# bilancia_smart.net
KiCad netlist of a schematic drawn in EAGLE
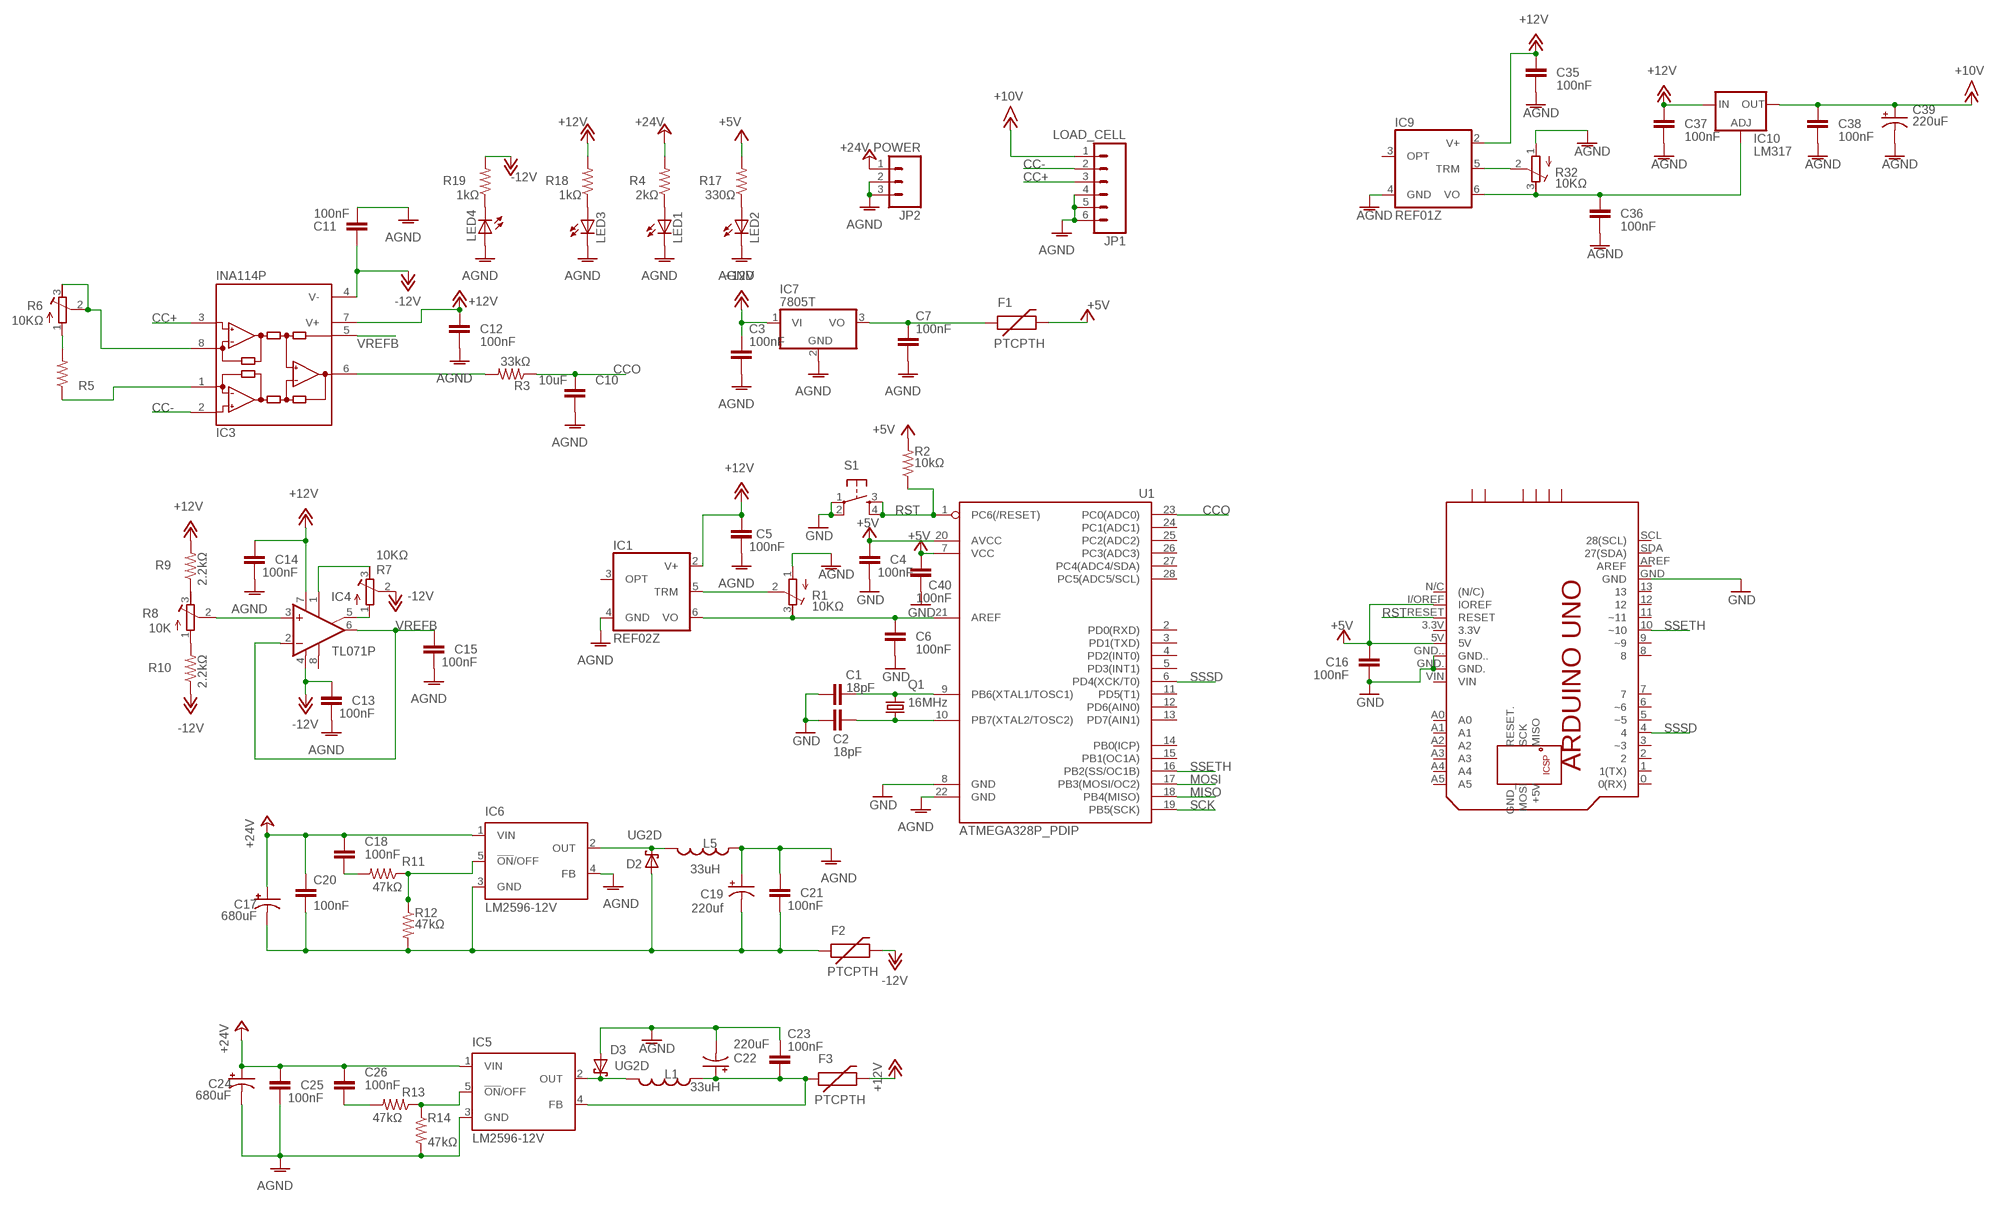
[diagram p0: schematic, sheet 1]

(export (version "E")
  (design (tool "Eeschema 10.0.6"))
  (components
    (comp (ref "C1")
      (value "18pF")
      (footprint "eagle-import:C2.5-2")
      (libsource (lib "eagle-import") (part "C2.5/2"))
    )
    (comp (ref "C2")
      (value "18pF")
      (footprint "eagle-import:C2.5-2")
      (libsource (lib "eagle-import") (part "C2.5/2"))
    )
    (comp (ref "C3")
      (value "100nF")
      (footprint "eagle-import:C2.5-2")
      (libsource (lib "eagle-import") (part "C2.5/2"))
    )
    (comp (ref "C4")
      (value "100nF")
      (footprint "eagle-import:C2.5-2")
      (libsource (lib "eagle-import") (part "C2.5/2"))
    )
    (comp (ref "C5")
      (value "100nF")
      (footprint "eagle-import:C2.5-2")
      (libsource (lib "eagle-import") (part "C2.5/2"))
    )
    (comp (ref "C6")
      (value "100nF")
      (footprint "eagle-import:C2.5-2")
      (libsource (lib "eagle-import") (part "C2.5/2"))
    )
    (comp (ref "C7")
      (value "100nF")
      (footprint "eagle-import:C2.5-2")
      (libsource (lib "eagle-import") (part "C2.5/2"))
    )
    (comp (ref "C10")
      (value "10uF")
      (footprint "eagle-import:C2.5-2")
      (libsource (lib "eagle-import") (part "C2.5/2"))
    )
    (comp (ref "C11")
      (value "100nF")
      (footprint "eagle-import:C2.5-2")
      (libsource (lib "eagle-import") (part "C2.5/2"))
    )
    (comp (ref "C12")
      (value "100nF")
      (footprint "eagle-import:C2.5-2")
      (libsource (lib "eagle-import") (part "C2.5/2"))
    )
    (comp (ref "C13")
      (value "100nF")
      (footprint "eagle-import:C2.5-2")
      (libsource (lib "eagle-import") (part "C2.5/2"))
    )
    (comp (ref "C14")
      (value "100nF")
      (footprint "eagle-import:C2.5-2")
      (libsource (lib "eagle-import") (part "C2.5/2"))
    )
    (comp (ref "C15")
      (value "100nF")
      (footprint "eagle-import:C2.5-2")
      (libsource (lib "eagle-import") (part "C2.5/2"))
    )
    (comp (ref "C16")
      (value "100nF")
      (footprint "eagle-import:C2.5-2")
      (libsource (lib "eagle-import") (part "C2.5/2"))
    )
    (comp (ref "C17")
      (value "680uF")
      (footprint "eagle-import:E5-8,5")
      (libsource (lib "eagle-import") (part "CPOL-USE5-8.5"))
    )
    (comp (ref "C18")
      (value "100nF")
      (footprint "eagle-import:C2.5-2")
      (libsource (lib "eagle-import") (part "C2.5/2"))
    )
    (comp (ref "C19")
      (value "220uf")
      (footprint "eagle-import:E5-8,5")
      (libsource (lib "eagle-import") (part "CPOL-USE5-8.5"))
    )
    (comp (ref "C20")
      (value "100nF")
      (footprint "eagle-import:C2.5-2")
      (libsource (lib "eagle-import") (part "C2.5/2"))
    )
    (comp (ref "C21")
      (value "100nF")
      (footprint "eagle-import:C2.5-2")
      (libsource (lib "eagle-import") (part "C2.5/2"))
    )
    (comp (ref "C22")
      (value "220uF")
      (footprint "eagle-import:E5-8,5")
      (libsource (lib "eagle-import") (part "CPOL-USE5-8.5"))
    )
    (comp (ref "C23")
      (value "100nF")
      (footprint "eagle-import:C2.5-2")
      (libsource (lib "eagle-import") (part "C2.5/2"))
    )
    (comp (ref "C24")
      (value "680uF")
      (footprint "eagle-import:E5-8,5")
      (libsource (lib "eagle-import") (part "CPOL-USE5-8.5"))
    )
    (comp (ref "C25")
      (value "100nF")
      (footprint "eagle-import:C2.5-2")
      (libsource (lib "eagle-import") (part "C2.5/2"))
    )
    (comp (ref "C26")
      (value "100nF")
      (footprint "eagle-import:C2.5-2")
      (libsource (lib "eagle-import") (part "C2.5/2"))
    )
    (comp (ref "C35")
      (value "100nF")
      (footprint "eagle-import:C2.5-2")
      (libsource (lib "eagle-import") (part "C2.5/2"))
    )
    (comp (ref "C36")
      (value "100nF")
      (footprint "eagle-import:C2.5-2")
      (libsource (lib "eagle-import") (part "C2.5/2"))
    )
    (comp (ref "C37")
      (value "100nF")
      (footprint "eagle-import:C2.5-2")
      (libsource (lib "eagle-import") (part "C2.5/2"))
    )
    (comp (ref "C38")
      (value "100nF")
      (footprint "eagle-import:C2.5-2")
      (libsource (lib "eagle-import") (part "C2.5/2"))
    )
    (comp (ref "C39")
      (value "220uF")
      (footprint "eagle-import:CPOL-RADIAL-100UF-25V")
      (libsource (lib "eagle-import") (part "CAP_POLPTH1"))
    )
    (comp (ref "C40")
      (value "100nF")
      (footprint "eagle-import:C2.5-2")
      (libsource (lib "eagle-import") (part "C2.5/2"))
    )
    (comp (ref "D2")
      (value "UG2D")
      (footprint "eagle-import:DO41-7")
      (libsource (lib "eagle-import") (part "SCHOTTKY-DIODEDO41-7"))
    )
    (comp (ref "D3")
      (value "UG2D")
      (footprint "eagle-import:DO41-7")
      (libsource (lib "eagle-import") (part "SCHOTTKY-DIODEDO41-7"))
    )
    (comp (ref "F1")
      (value "PTCPTH")
      (footprint "eagle-import:PTC")
      (libsource (lib "eagle-import") (part "PTCPTH"))
    )
    (comp (ref "F2")
      (value "PTCPTH")
      (footprint "eagle-import:PTC")
      (libsource (lib "eagle-import") (part "PTCPTH"))
    )
    (comp (ref "F3")
      (value "PTCPTH")
      (footprint "eagle-import:PTC")
      (libsource (lib "eagle-import") (part "PTCPTH"))
    )
    (comp (ref "IC1")
      (value "REF02Z")
      (footprint "eagle-import:DIL08")
      (libsource (lib "eagle-import") (part "REF02Z"))
    )
    (comp (ref "IC3")
      (value "INA114P")
      (footprint "eagle-import:DIL08")
      (fields (field (name "MF") "TEXAS INSTRUMENTS") (field (name "MPN") "INA114BP"))
      (libsource (lib "eagle-import") (part "INA114P"))
    )
    (comp (ref "IC4")
      (value "TL071P")
      (footprint "eagle-import:DIL08")
      (libsource (lib "eagle-import") (part "TL071P"))
    )
    (comp (ref "IC5")
      (value "LM2596-12V")
      (footprint "eagle-import:T05D")
      (fields (field (name "MPN") "LM2596T-ADJ/LF02"))
      (libsource (lib "eagle-import") (part "LM2596T"))
    )
    (comp (ref "IC6")
      (value "LM2596-12V")
      (footprint "eagle-import:T05D")
      (fields (field (name "MPN") "LM2596T-ADJ/LF02"))
      (libsource (lib "eagle-import") (part "LM2596T"))
    )
    (comp (ref "IC7")
      (value "7805T")
      (footprint "eagle-import:TO220H")
      (libsource (lib "eagle-import") (part "78T05"))
    )
    (comp (ref "IC9")
      (value "REF01Z")
      (footprint "eagle-import:DIL08")
      (libsource (lib "eagle-import") (part "REF01Z"))
    )
    (comp (ref "IC10")
      (value "LM317")
      (footprint "eagle-import:317TS")
      (libsource (lib "eagle-import") (part "LM317TS"))
    )
    (comp (ref "JP1")
      (value "LOAD_CELL")
      (footprint "eagle-import:1X06")
      (libsource (lib "eagle-import") (part "M06SIP"))
    )
    (comp (ref "JP2")
      (value "POWER")
      (footprint "eagle-import:1X03")
      (libsource (lib "eagle-import") (part "M03PTH"))
    )
    (comp (ref "L1")
      (value "33uH")
      (footprint "eagle-import:RLB0912")
      (libsource (lib "eagle-import") (part "INDUCTORRLB0912"))
    )
    (comp (ref "L5")
      (value "33uH")
      (footprint "eagle-import:RLB0912")
      (libsource (lib "eagle-import") (part "INDUCTORRLB0912"))
    )
    (comp (ref "LED1")
      (value "MINIMIDI_LED5MM")
      (footprint "eagle-import:MINIMIDI_LED5MM")
      (libsource (lib "eagle-import") (part "MINIMIDI_LED5MM"))
    )
    (comp (ref "LED2")
      (value "MINIMIDI_LED5MM")
      (footprint "eagle-import:MINIMIDI_LED5MM")
      (libsource (lib "eagle-import") (part "MINIMIDI_LED5MM"))
    )
    (comp (ref "LED3")
      (value "MINIMIDI_LED5MM")
      (footprint "eagle-import:MINIMIDI_LED5MM")
      (libsource (lib "eagle-import") (part "MINIMIDI_LED5MM"))
    )
    (comp (ref "LED4")
      (value "MINIMIDI_LED5MM")
      (footprint "eagle-import:MINIMIDI_LED5MM")
      (libsource (lib "eagle-import") (part "MINIMIDI_LED5MM"))
    )
    (comp (ref "PCB1")
      (value "ARDUINO_UNO")
      (footprint "eagle-import:ARDUINO_UNO")
      (libsource (lib "eagle-import") (part "ARDUINO_UNO"))
    )
    (comp (ref "Q1")
      (value "16MHz")
      (footprint "eagle-import:HC49_S")
      (libsource (lib "eagle-import") (part "CRYSTALHC49S"))
    )
    (comp (ref "R1")
      (value "10KΩ")
      (footprint "eagle-import:RTRIM64W")
      (libsource (lib "eagle-import") (part "R-TRIMM64W"))
    )
    (comp (ref "R2")
      (value "10kΩ")
      (footprint "eagle-import:0207_10")
      (libsource (lib "eagle-import") (part "R-US_0207/10"))
    )
    (comp (ref "R3")
      (value "33kΩ")
      (footprint "eagle-import:0207_10")
      (libsource (lib "eagle-import") (part "R-US_0207/10"))
    )
    (comp (ref "R4")
      (value "2kΩ")
      (footprint "eagle-import:0207_10")
      (libsource (lib "eagle-import") (part "R-US_0207/10"))
    )
    (comp (ref "R5")
      (value "R-US_0207/10")
      (footprint "eagle-import:0207_10")
      (libsource (lib "eagle-import") (part "R-US_0207/10"))
    )
    (comp (ref "R6")
      (value "10KΩ")
      (footprint "eagle-import:RTRIM64W")
      (libsource (lib "eagle-import") (part "R-TRIMM64W"))
    )
    (comp (ref "R7")
      (value "10KΩ")
      (footprint "eagle-import:RTRIM64W")
      (libsource (lib "eagle-import") (part "R-TRIMM64W"))
    )
    (comp (ref "R8")
      (value "10K")
      (footprint "eagle-import:RTRIM64W")
      (libsource (lib "eagle-import") (part "R-TRIMM64W"))
    )
    (comp (ref "R9")
      (value "2.2kΩ")
      (footprint "eagle-import:0207_10")
      (libsource (lib "eagle-import") (part "R-US_0207/10"))
    )
    (comp (ref "R10")
      (value "2.2kΩ")
      (footprint "eagle-import:0207_10")
      (libsource (lib "eagle-import") (part "R-US_0207/10"))
    )
    (comp (ref "R11")
      (value "47kΩ")
      (footprint "eagle-import:0207_2V")
      (libsource (lib "eagle-import") (part "R-US_0207/2V"))
    )
    (comp (ref "R12")
      (value "47kΩ")
      (footprint "eagle-import:0207_2V")
      (libsource (lib "eagle-import") (part "R-US_0207/2V"))
    )
    (comp (ref "R13")
      (value "47kΩ")
      (footprint "eagle-import:0207_2V")
      (libsource (lib "eagle-import") (part "R-US_0207/2V"))
    )
    (comp (ref "R14")
      (value "47kΩ")
      (footprint "eagle-import:0207_2V")
      (libsource (lib "eagle-import") (part "R-US_0207/2V"))
    )
    (comp (ref "R17")
      (value "330Ω")
      (footprint "eagle-import:0207_10")
      (libsource (lib "eagle-import") (part "R-US_0207/10"))
    )
    (comp (ref "R18")
      (value "1kΩ")
      (footprint "eagle-import:0207_10")
      (libsource (lib "eagle-import") (part "R-US_0207/10"))
    )
    (comp (ref "R19")
      (value "1kΩ")
      (footprint "eagle-import:0207_10")
      (libsource (lib "eagle-import") (part "R-US_0207/10"))
    )
    (comp (ref "R32")
      (value "10KΩ")
      (footprint "eagle-import:RTRIM64W")
      (libsource (lib "eagle-import") (part "R-TRIMM64W"))
    )
    (comp (ref "S1")
      (value "TAC_SWITCHPTH")
      (footprint "eagle-import:TACTILE-PTH")
      (libsource (lib "eagle-import") (part "TAC_SWITCHPTH"))
    )
    (comp (ref "U1")
      (value "ATMEGA328P_PDIP")
      (footprint "eagle-import:DIL28-3")
      (libsource (lib "eagle-import") (part "ATMEGA328P_PDIP"))
    )
  )
  (nets
    (net (code "1") (name "+5V") (class "Default")
      (node (ref "C16") (pin "2") (pinfunction "2_2") (pintype "passive"))
      (node (ref "C4") (pin "2") (pinfunction "2_2") (pintype "passive"))
      (node (ref "C40") (pin "2") (pinfunction "2_2") (pintype "passive"))
      (node (ref "F1") (pin "P$2") (pinfunction "2_P$2") (pintype "bidirectional"))
      (node (ref "PCB1") (pin "5V") (pinfunction "5V_5V") (pintype "bidirectional"))
      (node (ref "PCB1") (pin "I/OREF") (pinfunction "IOREF_I/OREF") (pintype "bidirectional"))
      (node (ref "R17") (pin "2") (pinfunction "2_2") (pintype "passive"))
      (node (ref "R2") (pin "2") (pinfunction "2_2") (pintype "passive"))
      (node (ref "U1") (pin "20") (pinfunction "AVCC_20") (pintype "bidirectional"))
      (node (ref "U1") (pin "7") (pinfunction "VCC_7") (pintype "bidirectional"))
    )
    (net (code "2") (name "+10V") (class "Default")
      (node (ref "C38") (pin "2") (pinfunction "2_2") (pintype "passive"))
      (node (ref "C39") (pin "1") (pinfunction "+_1") (pintype "passive"))
      (node (ref "IC10") (pin "2") (pinfunction "OUT_2") (pintype "passive"))
      (node (ref "JP1") (pin "1") (pinfunction "1_1") (pintype "passive"))
    )
    (net (code "3") (name "+12V") (class "Default")
      (node (ref "C12") (pin "2") (pinfunction "2_2") (pintype "passive"))
      (node (ref "C14") (pin "2") (pinfunction "2_2") (pintype "passive"))
      (node (ref "C3") (pin "2") (pinfunction "2_2") (pintype "passive"))
      (node (ref "C35") (pin "2") (pinfunction "2_2") (pintype "passive"))
      (node (ref "C37") (pin "2") (pinfunction "2_2") (pintype "passive"))
      (node (ref "C5") (pin "1") (pinfunction "1_1") (pintype "passive"))
      (node (ref "F3") (pin "P$2") (pinfunction "2_P$2") (pintype "bidirectional"))
      (node (ref "IC1") (pin "2") (pinfunction "V+_2") (pintype "power_in"))
      (node (ref "IC10") (pin "3") (pinfunction "IN_3") (pintype "input"))
      (node (ref "IC3") (pin "7") (pinfunction "V+_7") (pintype "power_in"))
      (node (ref "IC4") (pin "7") (pinfunction "V+_7") (pintype "power_in"))
      (node (ref "IC7") (pin "1") (pinfunction "VI_1") (pintype "input"))
      (node (ref "IC9") (pin "2") (pinfunction "V+_2") (pintype "power_in"))
      (node (ref "R18") (pin "2") (pinfunction "2_2") (pintype "passive"))
      (node (ref "R9") (pin "2") (pinfunction "2_2") (pintype "passive"))
    )
    (net (code "4") (name "+24V") (class "Default")
      (node (ref "C17") (pin "+") (pinfunction "+_+") (pintype "passive"))
      (node (ref "C18") (pin "1") (pinfunction "1_1") (pintype "passive"))
      (node (ref "C20") (pin "1") (pinfunction "1_1") (pintype "passive"))
      (node (ref "C24") (pin "+") (pinfunction "+_+") (pintype "passive"))
      (node (ref "C25") (pin "1") (pinfunction "1_1") (pintype "passive"))
      (node (ref "C26") (pin "1") (pinfunction "1_1") (pintype "passive"))
      (node (ref "IC5") (pin "1") (pinfunction "VIN_1") (pintype "input"))
      (node (ref "IC6") (pin "1") (pinfunction "VIN_1") (pintype "input"))
      (node (ref "JP2") (pin "1") (pinfunction "1_1") (pintype "passive"))
      (node (ref "R4") (pin "2") (pinfunction "2_2") (pintype "passive"))
    )
    (net (code "5") (name "-12V") (class "Default")
      (node (ref "C11") (pin "2") (pinfunction "2_2") (pintype "passive"))
      (node (ref "C13") (pin "2") (pinfunction "2_2") (pintype "passive"))
      (node (ref "F2") (pin "P$2") (pinfunction "2_P$2") (pintype "bidirectional"))
      (node (ref "IC3") (pin "4") (pinfunction "V-_4") (pintype "power_in"))
      (node (ref "IC4") (pin "4") (pinfunction "V-_4") (pintype "power_in"))
      (node (ref "R10") (pin "1") (pinfunction "1_1") (pintype "passive"))
      (node (ref "R19") (pin "2") (pinfunction "2_2") (pintype "passive"))
      (node (ref "R7") (pin "2") (pinfunction "S_2") (pintype "passive"))
    )
    (net (code "6") (name "/CC+") (class "Default")
      (node (ref "IC3") (pin "3") (pinfunction "+IN_3") (pintype "input"))
      (node (ref "JP1") (pin "3") (pinfunction "3_3") (pintype "passive"))
    )
    (net (code "7") (name "/CC-") (class "Default")
      (node (ref "IC3") (pin "2") (pinfunction "-IN_2") (pintype "input"))
      (node (ref "JP1") (pin "2") (pinfunction "2_2") (pintype "passive"))
    )
    (net (code "8") (name "/CCO") (class "Default")
      (node (ref "C10") (pin "2") (pinfunction "2_2") (pintype "passive"))
      (node (ref "R3") (pin "1") (pinfunction "1_1") (pintype "passive"))
      (node (ref "U1") (pin "23") (pinfunction "PC0(ADC0)_23") (pintype "bidirectional"))
    )
    (net (code "9") (name "/MISO") (class "Default")
      (node (ref "U1") (pin "18") (pinfunction "PB4(MISO)_18") (pintype "bidirectional"))
    )
    (net (code "10") (name "/MOSI") (class "Default")
      (node (ref "U1") (pin "17") (pinfunction "PB3(MOSI/OC2)_17") (pintype "bidirectional"))
    )
    (net (code "11") (name "/RST") (class "Default")
      (node (ref "PCB1") (pin "RESET") (pinfunction "RESET_RESET") (pintype "bidirectional"))
      (node (ref "R2") (pin "1") (pinfunction "1_1") (pintype "passive"))
      (node (ref "S1") (pin "3") (pinfunction "3_3") (pintype "passive"))
      (node (ref "S1") (pin "4") (pinfunction "4_4") (pintype "passive"))
      (node (ref "U1") (pin "1") (pinfunction "PC6(/RESET)_1") (pintype "bidirectional"))
    )
    (net (code "12") (name "/SCK") (class "Default")
      (node (ref "U1") (pin "19") (pinfunction "PB5(SCK)_19") (pintype "bidirectional"))
    )
    (net (code "13") (name "/SSETH") (class "Default")
      (node (ref "PCB1") (pin "10") (pinfunction "~{10}_10") (pintype "bidirectional"))
      (node (ref "U1") (pin "16") (pinfunction "PB2(SS/OC1B)_16") (pintype "bidirectional"))
    )
    (net (code "14") (name "/SSSD") (class "Default")
      (node (ref "PCB1") (pin "4") (pinfunction "4_4") (pintype "bidirectional"))
      (node (ref "U1") (pin "6") (pinfunction "PD4(XCK/T0)_6") (pintype "bidirectional"))
    )
    (net (code "15") (name "/VREFB") (class "Default")
      (node (ref "C15") (pin "2") (pinfunction "2_2") (pintype "passive"))
      (node (ref "IC3") (pin "5") (pinfunction "REF_5") (pintype "passive"))
      (node (ref "IC4") (pin "2") (pinfunction "-IN_2") (pintype "input"))
      (node (ref "IC4") (pin "6") (pinfunction "OUT_6") (pintype "output"))
    )
    (net (code "16") (name "AGND") (class "Default")
      (node (ref "C10") (pin "1") (pinfunction "1_1") (pintype "passive"))
      (node (ref "C11") (pin "1") (pinfunction "1_1") (pintype "passive"))
      (node (ref "C12") (pin "1") (pinfunction "1_1") (pintype "passive"))
      (node (ref "C13") (pin "1") (pinfunction "1_1") (pintype "passive"))
      (node (ref "C14") (pin "1") (pinfunction "1_1") (pintype "passive"))
      (node (ref "C15") (pin "1") (pinfunction "1_1") (pintype "passive"))
      (node (ref "C19") (pin "+") (pinfunction "+_+") (pintype "passive"))
      (node (ref "C21") (pin "1") (pinfunction "1_1") (pintype "passive"))
      (node (ref "C22") (pin "-") (pinfunction "-_-") (pintype "passive"))
      (node (ref "C23") (pin "2") (pinfunction "2_2") (pintype "passive"))
      (node (ref "C24") (pin "-") (pinfunction "-_-") (pintype "passive"))
      (node (ref "C25") (pin "2") (pinfunction "2_2") (pintype "passive"))
      (node (ref "C3") (pin "1") (pinfunction "1_1") (pintype "passive"))
      (node (ref "C35") (pin "1") (pinfunction "1_1") (pintype "passive"))
      (node (ref "C36") (pin "1") (pinfunction "1_1") (pintype "passive"))
      (node (ref "C37") (pin "1") (pinfunction "1_1") (pintype "passive"))
      (node (ref "C38") (pin "1") (pinfunction "1_1") (pintype "passive"))
      (node (ref "C39") (pin "2") (pinfunction "-_2") (pintype "passive"))
      (node (ref "C5") (pin "2") (pinfunction "2_2") (pintype "passive"))
      (node (ref "C7") (pin "1") (pinfunction "1_1") (pintype "passive"))
      (node (ref "D3") (pin "A") (pinfunction "A_A") (pintype "passive"))
      (node (ref "IC1") (pin "4") (pinfunction "GND_4") (pintype "power_in"))
      (node (ref "IC5") (pin "3") (pinfunction "GND_3") (pintype "power_in"))
      (node (ref "IC6") (pin "4") (pinfunction "FB_4") (pintype "input"))
      (node (ref "IC7") (pin "2") (pinfunction "GND_2") (pintype "passive"))
      (node (ref "IC9") (pin "4") (pinfunction "GND_4") (pintype "power_in"))
      (node (ref "JP1") (pin "4") (pinfunction "4_4") (pintype "passive"))
      (node (ref "JP1") (pin "5") (pinfunction "5_5") (pintype "passive"))
      (node (ref "JP1") (pin "6") (pinfunction "6_6") (pintype "passive"))
      (node (ref "JP2") (pin "2") (pinfunction "2_2") (pintype "passive"))
      (node (ref "JP2") (pin "3") (pinfunction "3_3") (pintype "passive"))
      (node (ref "L5") (pin "1") (pinfunction "1_1") (pintype "passive"))
      (node (ref "LED1") (pin "K") (pinfunction "C_K") (pintype "passive"))
      (node (ref "LED2") (pin "K") (pinfunction "C_K") (pintype "passive"))
      (node (ref "LED3") (pin "K") (pinfunction "C_K") (pintype "passive"))
      (node (ref "LED4") (pin "A") (pinfunction "A_A") (pintype "passive"))
      (node (ref "R1") (pin "1") (pinfunction "E_1") (pintype "passive"))
      (node (ref "R14") (pin "2") (pinfunction "2_2") (pintype "passive"))
      (node (ref "R32") (pin "1") (pinfunction "E_1") (pintype "passive"))
      (node (ref "U1") (pin "22") (pinfunction "GND_22") (pintype "bidirectional"))
    )
    (net (code "17") (name "GND") (class "Default")
      (node (ref "C1") (pin "1") (pinfunction "1_1") (pintype "passive"))
      (node (ref "C16") (pin "1") (pinfunction "1_1") (pintype "passive"))
      (node (ref "C2") (pin "1") (pinfunction "1_1") (pintype "passive"))
      (node (ref "C4") (pin "1") (pinfunction "1_1") (pintype "passive"))
      (node (ref "C40") (pin "1") (pinfunction "1_1") (pintype "passive"))
      (node (ref "C6") (pin "1") (pinfunction "1_1") (pintype "passive"))
      (node (ref "PCB1") (pin "GND") (pinfunction "GND_GND") (pintype "bidirectional"))
      (node (ref "PCB1") (pin "GND.") (pinfunction "GND._GND.") (pintype "bidirectional"))
      (node (ref "PCB1") (pin "GND..") (pinfunction "GND.._GND..") (pintype "bidirectional"))
      (node (ref "S1") (pin "1") (pinfunction "1_1") (pintype "passive"))
      (node (ref "S1") (pin "2") (pinfunction "2_2") (pintype "passive"))
      (node (ref "U1") (pin "8") (pinfunction "GND_8") (pintype "bidirectional"))
    )
    (net (code "18") (name "Net-(C18-Pad2)") (class "Default")
      (node (ref "C18") (pin "2") (pinfunction "2_2") (pintype "passive"))
      (node (ref "R11") (pin "2") (pinfunction "2_2") (pintype "passive"))
    )
    (net (code "19") (name "Net-(C26-Pad2)") (class "Default")
      (node (ref "C26") (pin "2") (pinfunction "2_2") (pintype "passive"))
      (node (ref "R13") (pin "2") (pinfunction "2_2") (pintype "passive"))
    )
    (net (code "20") (name "Net-(F1-1)") (class "Default")
      (node (ref "C7") (pin "2") (pinfunction "2_2") (pintype "passive"))
      (node (ref "F1") (pin "P$1") (pinfunction "1_P$1") (pintype "bidirectional"))
      (node (ref "IC7") (pin "3") (pinfunction "VO_3") (pintype "passive"))
    )
    (net (code "21") (name "Net-(F2-1)") (class "Default")
      (node (ref "C17") (pin "-") (pinfunction "-_-") (pintype "passive"))
      (node (ref "C19") (pin "-") (pinfunction "-_-") (pintype "passive"))
      (node (ref "C20") (pin "2") (pinfunction "2_2") (pintype "passive"))
      (node (ref "C21") (pin "2") (pinfunction "2_2") (pintype "passive"))
      (node (ref "D2") (pin "A") (pinfunction "A_A") (pintype "passive"))
      (node (ref "F2") (pin "P$1") (pinfunction "1_P$1") (pintype "bidirectional"))
      (node (ref "IC6") (pin "3") (pinfunction "GND_3") (pintype "power_in"))
      (node (ref "R12") (pin "2") (pinfunction "2_2") (pintype "passive"))
    )
    (net (code "22") (name "Net-(F3-1)") (class "Default")
      (node (ref "C22") (pin "+") (pinfunction "+_+") (pintype "passive"))
      (node (ref "C23") (pin "1") (pinfunction "1_1") (pintype "passive"))
      (node (ref "F3") (pin "P$1") (pinfunction "1_P$1") (pintype "bidirectional"))
      (node (ref "IC5") (pin "4") (pinfunction "FB_4") (pintype "input"))
      (node (ref "L1") (pin "1") (pinfunction "1_1") (pintype "passive"))
    )
    (net (code "23") (name "Net-(IC1-TRM)") (class "Default")
      (node (ref "IC1") (pin "5") (pinfunction "TRM_5") (pintype "input"))
      (node (ref "R1") (pin "2") (pinfunction "S_2") (pintype "passive"))
    )
    (net (code "24") (name "Net-(IC1-VO)") (class "Default")
      (node (ref "C6") (pin "2") (pinfunction "2_2") (pintype "passive"))
      (node (ref "IC1") (pin "6") (pinfunction "VO_6") (pintype "output"))
      (node (ref "R1") (pin "3") (pinfunction "A_3") (pintype "passive"))
      (node (ref "U1") (pin "21") (pinfunction "AREF_21") (pintype "bidirectional"))
    )
    (net (code "25") (name "Net-(IC3-OUT)") (class "Default")
      (node (ref "IC3") (pin "6") (pinfunction "OUT_6") (pintype "output"))
      (node (ref "R3") (pin "2") (pinfunction "2_2") (pintype "passive"))
    )
    (net (code "26") (name "Net-(IC3-RG-Pad1)") (class "Default")
      (node (ref "IC3") (pin "1") (pinfunction "RG_1") (pintype "passive"))
      (node (ref "R5") (pin "1") (pinfunction "1_1") (pintype "passive"))
    )
    (net (code "27") (name "Net-(IC4-+IN)") (class "Default")
      (node (ref "IC4") (pin "3") (pinfunction "+IN_3") (pintype "input"))
      (node (ref "R8") (pin "2") (pinfunction "S_2") (pintype "passive"))
    )
    (net (code "28") (name "Net-(IC4-ON1)") (class "Default")
      (node (ref "IC4") (pin "1") (pinfunction "ON1_1") (pintype "passive"))
      (node (ref "R7") (pin "3") (pinfunction "A_3") (pintype "passive"))
    )
    (net (code "29") (name "Net-(IC4-ON2)") (class "Default")
      (node (ref "IC4") (pin "5") (pinfunction "ON2_5") (pintype "passive"))
      (node (ref "R7") (pin "1") (pinfunction "E_1") (pintype "passive"))
    )
    (net (code "30") (name "Net-(IC5-OUT)") (class "Default")
      (node (ref "D3") (pin "C") (pinfunction "C_C") (pintype "passive"))
      (node (ref "IC5") (pin "2") (pinfunction "OUT_2") (pintype "output"))
      (node (ref "L1") (pin "2") (pinfunction "2_2") (pintype "passive"))
    )
    (net (code "31") (name "Net-(IC5-~{ON}{slash}OFF)") (class "Default")
      (node (ref "IC5") (pin "5") (pinfunction "~{ON}/OFF_5") (pintype "input"))
      (node (ref "R13") (pin "1") (pinfunction "1_1") (pintype "passive"))
      (node (ref "R14") (pin "1") (pinfunction "1_1") (pintype "passive"))
    )
    (net (code "32") (name "Net-(IC6-OUT)") (class "Default")
      (node (ref "D2") (pin "C") (pinfunction "C_C") (pintype "passive"))
      (node (ref "IC6") (pin "2") (pinfunction "OUT_2") (pintype "output"))
      (node (ref "L5") (pin "2") (pinfunction "2_2") (pintype "passive"))
    )
    (net (code "33") (name "Net-(IC6-~{ON}{slash}OFF)") (class "Default")
      (node (ref "IC6") (pin "5") (pinfunction "~{ON}/OFF_5") (pintype "input"))
      (node (ref "R11") (pin "1") (pinfunction "1_1") (pintype "passive"))
      (node (ref "R12") (pin "1") (pinfunction "1_1") (pintype "passive"))
    )
    (net (code "34") (name "Net-(IC9-TRM)") (class "Default")
      (node (ref "IC9") (pin "5") (pinfunction "TRM_5") (pintype "input"))
      (node (ref "R32") (pin "2") (pinfunction "S_2") (pintype "passive"))
    )
    (net (code "35") (name "Net-(IC10-ADJ)") (class "Default")
      (node (ref "C36") (pin "2") (pinfunction "2_2") (pintype "passive"))
      (node (ref "IC10") (pin "1") (pinfunction "ADJ_1") (pintype "input"))
      (node (ref "IC9") (pin "6") (pinfunction "VO_6") (pintype "output"))
      (node (ref "R32") (pin "3") (pinfunction "A_3") (pintype "passive"))
    )
    (net (code "36") (name "Net-(LED1-PadA)") (class "Default")
      (node (ref "LED1") (pin "A") (pinfunction "A_A") (pintype "passive"))
      (node (ref "R4") (pin "1") (pinfunction "1_1") (pintype "passive"))
    )
    (net (code "37") (name "Net-(LED2-PadA)") (class "Default")
      (node (ref "LED2") (pin "A") (pinfunction "A_A") (pintype "passive"))
      (node (ref "R17") (pin "1") (pinfunction "1_1") (pintype "passive"))
    )
    (net (code "38") (name "Net-(LED3-PadA)") (class "Default")
      (node (ref "LED3") (pin "A") (pinfunction "A_A") (pintype "passive"))
      (node (ref "R18") (pin "1") (pinfunction "1_1") (pintype "passive"))
    )
    (net (code "39") (name "Net-(LED4-C)") (class "Default")
      (node (ref "LED4") (pin "K") (pinfunction "C_K") (pintype "passive"))
      (node (ref "R19") (pin "1") (pinfunction "1_1") (pintype "passive"))
    )
    (net (code "40") (name "Net-(R6-A)") (class "Default")
      (node (ref "IC3") (pin "8") (pinfunction "RG_8") (pintype "passive"))
      (node (ref "R6") (pin "2") (pinfunction "S_2") (pintype "passive"))
      (node (ref "R6") (pin "3") (pinfunction "A_3") (pintype "passive"))
    )
    (net (code "41") (name "Net-(R6-E)") (class "Default")
      (node (ref "R5") (pin "2") (pinfunction "2_2") (pintype "passive"))
      (node (ref "R6") (pin "1") (pinfunction "E_1") (pintype "passive"))
    )
    (net (code "42") (name "Net-(R8-A)") (class "Default")
      (node (ref "R8") (pin "3") (pinfunction "A_3") (pintype "passive"))
      (node (ref "R9") (pin "1") (pinfunction "1_1") (pintype "passive"))
    )
    (net (code "43") (name "Net-(R8-E)") (class "Default")
      (node (ref "R10") (pin "2") (pinfunction "2_2") (pintype "passive"))
      (node (ref "R8") (pin "1") (pinfunction "E_1") (pintype "passive"))
    )
    (net (code "44") (name "Net-(U1-PB6(XTAL1{slash}TOSC1))") (class "Default")
      (node (ref "C1") (pin "2") (pinfunction "2_2") (pintype "passive"))
      (node (ref "Q1") (pin "1") (pinfunction "1_1") (pintype "passive"))
      (node (ref "U1") (pin "9") (pinfunction "PB6(XTAL1/TOSC1)_9") (pintype "bidirectional"))
    )
    (net (code "45") (name "Net-(U1-PB7(XTAL2{slash}TOSC2))") (class "Default")
      (node (ref "C2") (pin "2") (pinfunction "2_2") (pintype "passive"))
      (node (ref "Q1") (pin "2") (pinfunction "2_2") (pintype "passive"))
      (node (ref "U1") (pin "10") (pinfunction "PB7(XTAL2/TOSC2)_10") (pintype "bidirectional"))
    )
    (net (code "46") (name "unconnected-(IC1-OPT-Pad3)") (class "Default")
      (node (ref "IC1") (pin "3") (pinfunction "OPT_3") (pintype "output"))
    )
    (net (code "47") (name "unconnected-(IC4-OPT-Pad8)") (class "Default")
      (node (ref "IC4") (pin "8") (pinfunction "OPT_8") (pintype "passive"))
    )
    (net (code "48") (name "unconnected-(IC9-OPT-Pad3)") (class "Default")
      (node (ref "IC9") (pin "3") (pinfunction "OPT_3") (pintype "output"))
    )
    (net (code "49") (name "unconnected-(PCB1-(N{slash}C)-PadN{slash}C)") (class "Default")
      (node (ref "PCB1") (pin "N/C") (pinfunction "(N/C)_N/C") (pintype "bidirectional"))
    )
    (net (code "50") (name "unconnected-(PCB1-0(RX)-Pad0)") (class "Default")
      (node (ref "PCB1") (pin "0") (pinfunction "0(RX)_0") (pintype "bidirectional"))
    )
    (net (code "51") (name "unconnected-(PCB1-1(TX)-Pad1)") (class "Default")
      (node (ref "PCB1") (pin "1") (pinfunction "1(TX)_1") (pintype "bidirectional"))
    )
    (net (code "52") (name "unconnected-(PCB1-27(SDA)-PadSDA)") (class "Default")
      (node (ref "PCB1") (pin "SDA") (pinfunction "27(SDA)_SDA") (pintype "bidirectional"))
    )
    (net (code "53") (name "unconnected-(PCB1-28(SCL)-PadSCL)") (class "Default")
      (node (ref "PCB1") (pin "SCL") (pinfunction "28(SCL)_SCL") (pintype "bidirectional"))
    )
    (net (code "54") (name "unconnected-(PCB1-Pad+5V)") (class "Default")
      (node (ref "PCB1") (pin "+5V") (pinfunction "+5V_+5V") (pintype "bidirectional"))
    )
    (net (code "55") (name "unconnected-(PCB1-Pad2)") (class "Default")
      (node (ref "PCB1") (pin "2") (pinfunction "2_2") (pintype "bidirectional"))
    )
    (net (code "56") (name "unconnected-(PCB1-Pad3.3V)") (class "Default")
      (node (ref "PCB1") (pin "3.3V") (pinfunction "3.3V_3.3V") (pintype "bidirectional"))
    )
    (net (code "57") (name "unconnected-(PCB1-Pad7)") (class "Default")
      (node (ref "PCB1") (pin "7") (pinfunction "7_7") (pintype "bidirectional"))
    )
    (net (code "58") (name "unconnected-(PCB1-Pad8)") (class "Default")
      (node (ref "PCB1") (pin "8") (pinfunction "8_8") (pintype "bidirectional"))
    )
    (net (code "59") (name "unconnected-(PCB1-Pad12)") (class "Default")
      (node (ref "PCB1") (pin "12") (pinfunction "12_12") (pintype "bidirectional"))
    )
    (net (code "60") (name "unconnected-(PCB1-Pad13)") (class "Default")
      (node (ref "PCB1") (pin "13") (pinfunction "13_13") (pintype "bidirectional"))
    )
    (net (code "61") (name "unconnected-(PCB1-Pad<PWR>+V)") (class "Default")
      (node (ref "PCB1") (pin "<PWR>+V") (pinfunction "<PWR>+V_<PWR>+V") (pintype "bidirectional"))
    )
    (net (code "62") (name "unconnected-(PCB1-Pad<PWR>-V)") (class "Default")
      (node (ref "PCB1") (pin "<PWR>-V") (pinfunction "<PWR>-V_<PWR>-V") (pintype "bidirectional"))
    )
    (net (code "63") (name "unconnected-(PCB1-Pad<USB>+V)") (class "Default")
      (node (ref "PCB1") (pin "<USB>+V") (pinfunction "<USB>+V_<USB>+V") (pintype "bidirectional"))
    )
    (net (code "64") (name "unconnected-(PCB1-Pad<USB>D+)") (class "Default")
      (node (ref "PCB1") (pin "<USB>D+") (pinfunction "<USB>D+_<USB>D+") (pintype "bidirectional"))
    )
    (net (code "65") (name "unconnected-(PCB1-Pad<USB>D-)") (class "Default")
      (node (ref "PCB1") (pin "<USB>D-") (pinfunction "<USB>D-_<USB>D-") (pintype "bidirectional"))
    )
    (net (code "66") (name "unconnected-(PCB1-Pad<USB>GND)") (class "Default")
      (node (ref "PCB1") (pin "<USB>GND") (pinfunction "<USB>GND_<USB>GND") (pintype "bidirectional"))
    )
    (net (code "67") (name "unconnected-(PCB1-PadA0)") (class "Default")
      (node (ref "PCB1") (pin "A0") (pinfunction "A0_A0") (pintype "bidirectional"))
    )
    (net (code "68") (name "unconnected-(PCB1-PadA1)") (class "Default")
      (node (ref "PCB1") (pin "A1") (pinfunction "A1_A1") (pintype "bidirectional"))
    )
    (net (code "69") (name "unconnected-(PCB1-PadA2)") (class "Default")
      (node (ref "PCB1") (pin "A2") (pinfunction "A2_A2") (pintype "bidirectional"))
    )
    (net (code "70") (name "unconnected-(PCB1-PadA3)") (class "Default")
      (node (ref "PCB1") (pin "A3") (pinfunction "A3_A3") (pintype "bidirectional"))
    )
    (net (code "71") (name "unconnected-(PCB1-PadA4)") (class "Default")
      (node (ref "PCB1") (pin "A4") (pinfunction "A4_A4") (pintype "bidirectional"))
    )
    (net (code "72") (name "unconnected-(PCB1-PadA5)") (class "Default")
      (node (ref "PCB1") (pin "A5") (pinfunction "A5_A5") (pintype "bidirectional"))
    )
    (net (code "73") (name "unconnected-(PCB1-PadAREF)") (class "Default")
      (node (ref "PCB1") (pin "AREF") (pinfunction "AREF_AREF") (pintype "bidirectional"))
    )
    (net (code "74") (name "unconnected-(PCB1-PadGND_)") (class "Default")
      (node (ref "PCB1") (pin "GND_") (pinfunction "GND__GND_") (pintype "bidirectional"))
    )
    (net (code "75") (name "unconnected-(PCB1-PadMISO)") (class "Default")
      (node (ref "PCB1") (pin "MISO") (pinfunction "MISO_MISO") (pintype "bidirectional"))
    )
    (net (code "76") (name "unconnected-(PCB1-PadMOSI)") (class "Default")
      (node (ref "PCB1") (pin "MOSI") (pinfunction "MOSI_MOSI") (pintype "bidirectional"))
    )
    (net (code "77") (name "unconnected-(PCB1-PadRESET.)") (class "Default")
      (node (ref "PCB1") (pin "RESET.") (pinfunction "RESET._RESET.") (pintype "bidirectional"))
    )
    (net (code "78") (name "unconnected-(PCB1-PadSCK)") (class "Default")
      (node (ref "PCB1") (pin "SCK") (pinfunction "SCK_SCK") (pintype "bidirectional"))
    )
    (net (code "79") (name "unconnected-(PCB1-PadVIN)") (class "Default")
      (node (ref "PCB1") (pin "VIN") (pinfunction "VIN_VIN") (pintype "bidirectional"))
    )
    (net (code "80") (name "unconnected-(PCB1-~{3}-Pad3)") (class "Default")
      (node (ref "PCB1") (pin "3") (pinfunction "~{3}_3") (pintype "bidirectional"))
    )
    (net (code "81") (name "unconnected-(PCB1-~{5}-Pad5)") (class "Default")
      (node (ref "PCB1") (pin "5") (pinfunction "~{5}_5") (pintype "bidirectional"))
    )
    (net (code "82") (name "unconnected-(PCB1-~{6}-Pad6)") (class "Default")
      (node (ref "PCB1") (pin "6") (pinfunction "~{6}_6") (pintype "bidirectional"))
    )
    (net (code "83") (name "unconnected-(PCB1-~{9}-Pad9)") (class "Default")
      (node (ref "PCB1") (pin "9") (pinfunction "~{9}_9") (pintype "bidirectional"))
    )
    (net (code "84") (name "unconnected-(PCB1-~{11}-Pad11)") (class "Default")
      (node (ref "PCB1") (pin "11") (pinfunction "~{11}_11") (pintype "bidirectional"))
    )
    (net (code "85") (name "unconnected-(U1-PB0(ICP)-Pad14)") (class "Default")
      (node (ref "U1") (pin "14") (pinfunction "PB0(ICP)_14") (pintype "bidirectional"))
    )
    (net (code "86") (name "unconnected-(U1-PB1(OC1A)-Pad15)") (class "Default")
      (node (ref "U1") (pin "15") (pinfunction "PB1(OC1A)_15") (pintype "bidirectional"))
    )
    (net (code "87") (name "unconnected-(U1-PC1(ADC1)-Pad24)") (class "Default")
      (node (ref "U1") (pin "24") (pinfunction "PC1(ADC1)_24") (pintype "bidirectional"))
    )
    (net (code "88") (name "unconnected-(U1-PC2(ADC2)-Pad25)") (class "Default")
      (node (ref "U1") (pin "25") (pinfunction "PC2(ADC2)_25") (pintype "bidirectional"))
    )
    (net (code "89") (name "unconnected-(U1-PC3(ADC3)-Pad26)") (class "Default")
      (node (ref "U1") (pin "26") (pinfunction "PC3(ADC3)_26") (pintype "bidirectional"))
    )
    (net (code "90") (name "unconnected-(U1-PC4(ADC4{slash}SDA)-Pad27)") (class "Default")
      (node (ref "U1") (pin "27") (pinfunction "PC4(ADC4/SDA)_27") (pintype "bidirectional"))
    )
    (net (code "91") (name "unconnected-(U1-PC5(ADC5{slash}SCL)-Pad28)") (class "Default")
      (node (ref "U1") (pin "28") (pinfunction "PC5(ADC5/SCL)_28") (pintype "bidirectional"))
    )
    (net (code "92") (name "unconnected-(U1-PD0(RXD)-Pad2)") (class "Default")
      (node (ref "U1") (pin "2") (pinfunction "PD0(RXD)_2") (pintype "bidirectional"))
    )
    (net (code "93") (name "unconnected-(U1-PD1(TXD)-Pad3)") (class "Default")
      (node (ref "U1") (pin "3") (pinfunction "PD1(TXD)_3") (pintype "bidirectional"))
    )
    (net (code "94") (name "unconnected-(U1-PD2(INT0)-Pad4)") (class "Default")
      (node (ref "U1") (pin "4") (pinfunction "PD2(INT0)_4") (pintype "bidirectional"))
    )
    (net (code "95") (name "unconnected-(U1-PD3(INT1)-Pad5)") (class "Default")
      (node (ref "U1") (pin "5") (pinfunction "PD3(INT1)_5") (pintype "bidirectional"))
    )
    (net (code "96") (name "unconnected-(U1-PD5(T1)-Pad11)") (class "Default")
      (node (ref "U1") (pin "11") (pinfunction "PD5(T1)_11") (pintype "bidirectional"))
    )
    (net (code "97") (name "unconnected-(U1-PD6(AIN0)-Pad12)") (class "Default")
      (node (ref "U1") (pin "12") (pinfunction "PD6(AIN0)_12") (pintype "bidirectional"))
    )
    (net (code "98") (name "unconnected-(U1-PD7(AIN1)-Pad13)") (class "Default")
      (node (ref "U1") (pin "13") (pinfunction "PD7(AIN1)_13") (pintype "bidirectional"))
    )
  )
)
